# uvc_air_filter_psu.net
KiCad netlist of a schematic drawn in EAGLE
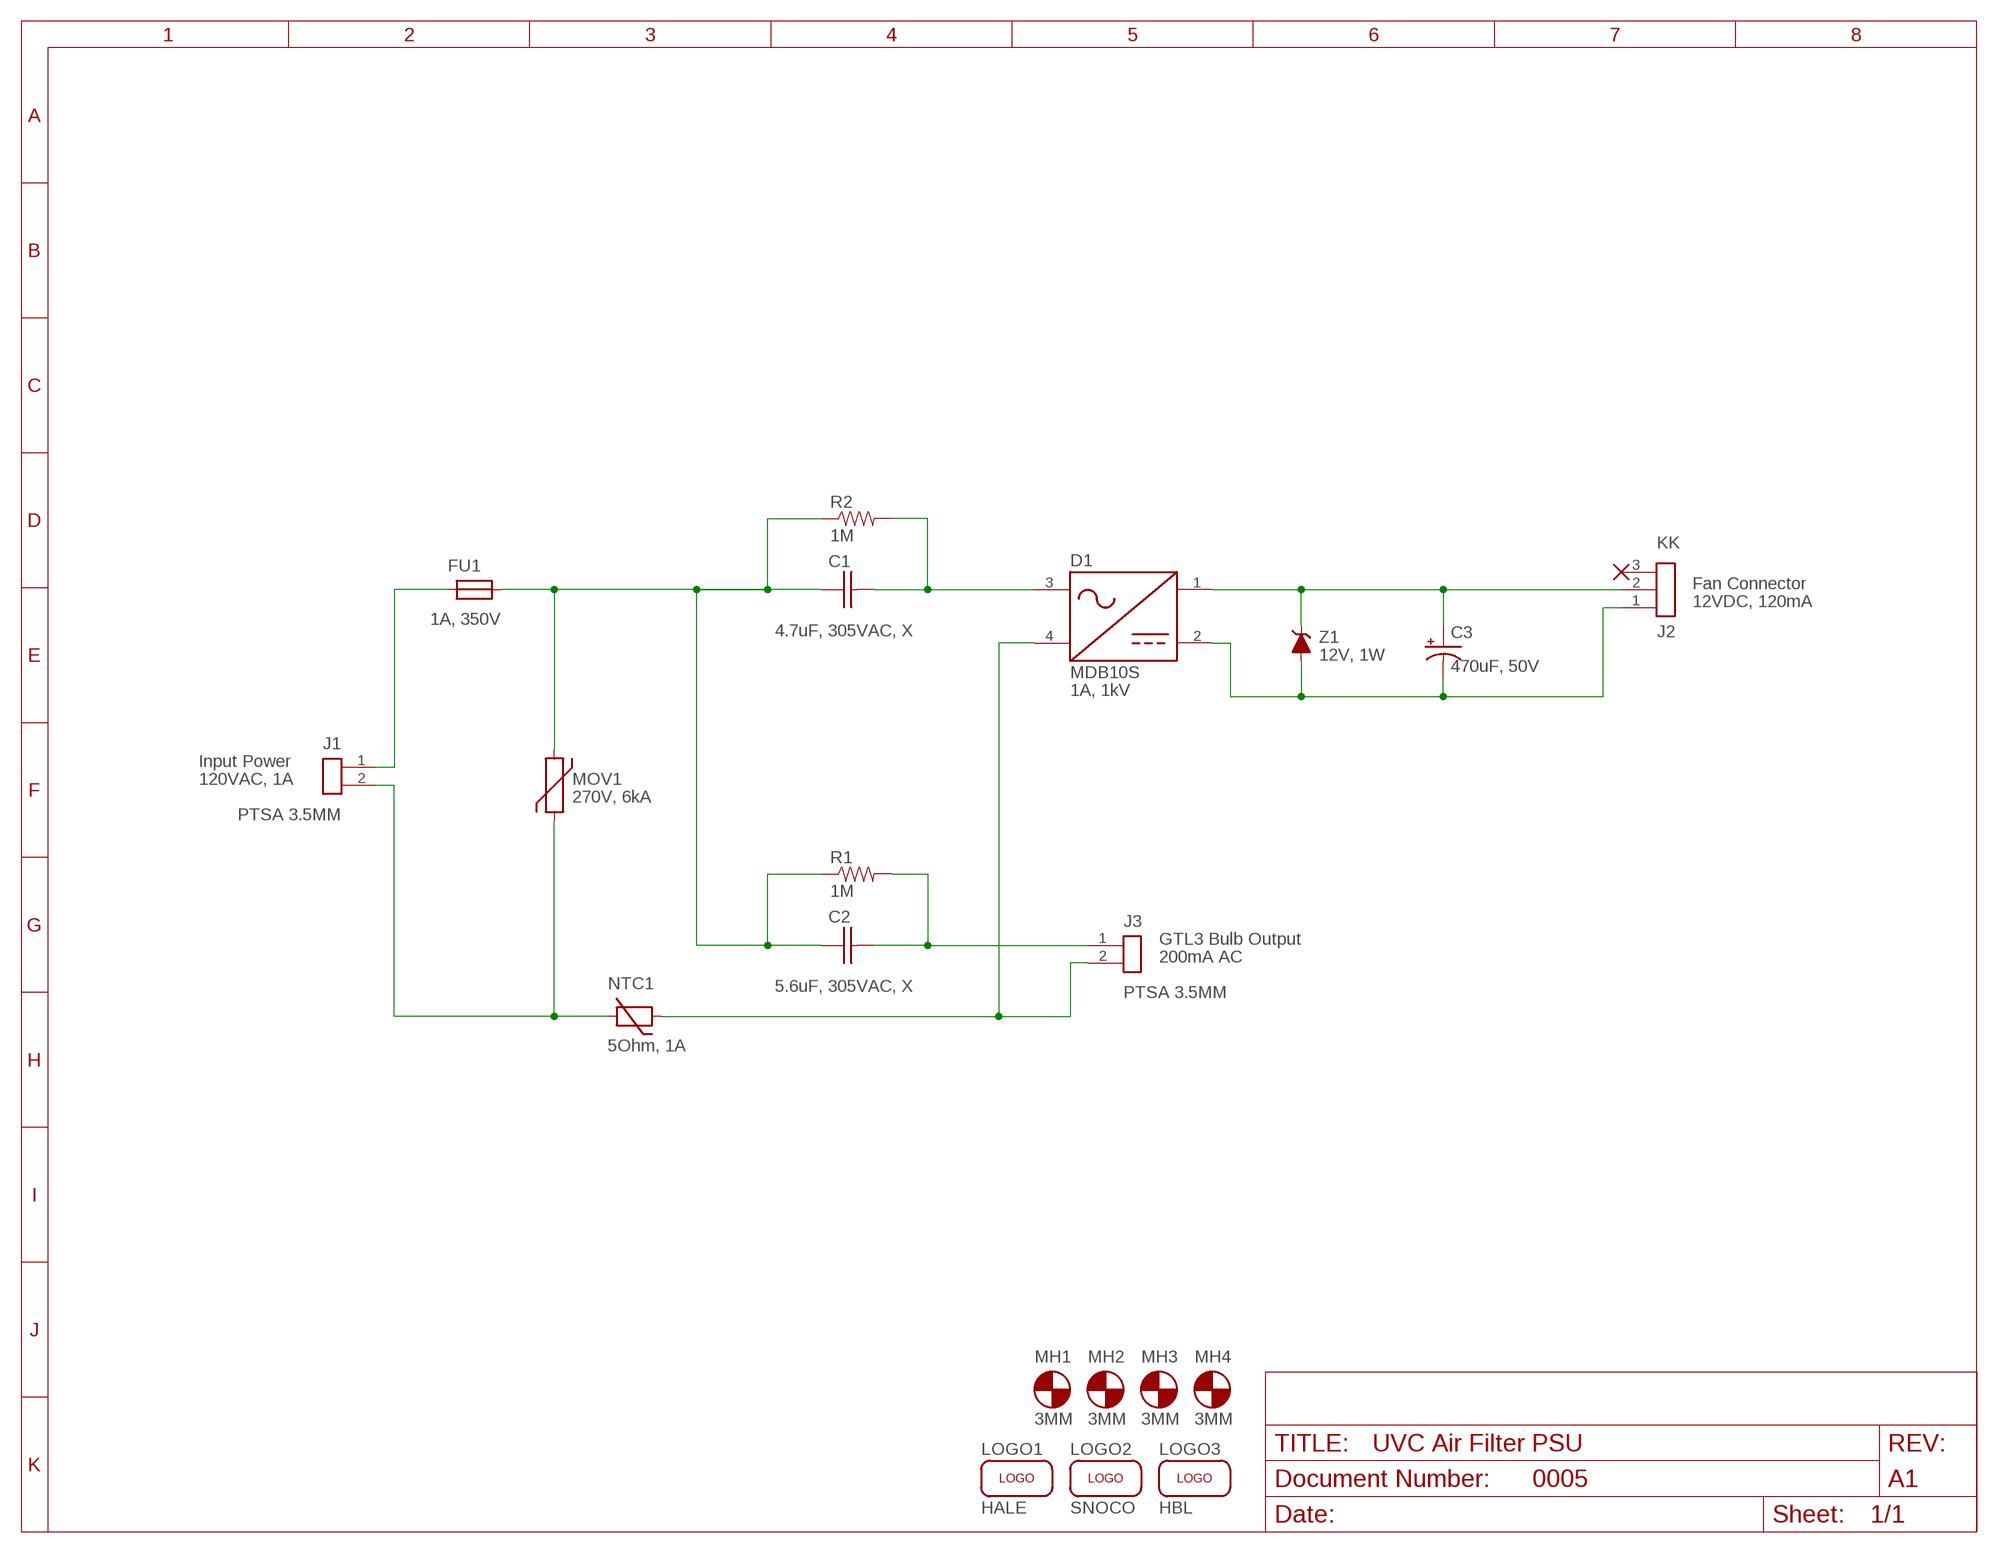
[diagram p0: schematic, sheet 1]

(export (version "E")
  (design (tool "Eeschema 10.0.6"))
  (components
    (comp (ref "C1")
      (value "4.7uF, 305VAC, X")
      (footprint "eagle-import:CAP-27.5MM")
      (fields (field (name "MFG") "TDK Electronics Inc."))
      (libsource (lib "eagle-import") (part "C-27.5MM-4.7UF/305VAC"))
    )
    (comp (ref "C2")
      (value "5.6uF, 305VAC, X")
      (footprint "eagle-import:CAP-27.5MM")
      (fields (field (name "MFG") "TDK Electronics Inc."))
      (libsource (lib "eagle-import") (part "C-27.5MM-5.6UF/305VAC"))
    )
    (comp (ref "C3")
      (value "470uF, 50V")
      (footprint "eagle-import:CAP-5MM-10MM")
      (fields
        (field (name "MFG") "Panasonic Electronic Components")
        (field (name "DIGIKEY") "P5185-ND")
        (field (name "PN") "ECA-1HM471")
      )
      (libsource (lib "eagle-import") (part "C-POL-10MM-470UF/50V"))
    )
    (comp (ref "D1")
      (value "1A, 1kV")
      (footprint "eagle-import:TSSOP-4")
      (fields (field (name "MFG") "ON Semiconductor"))
      (libsource (lib "eagle-import") (part "RECTIFIER-MDB-MDB10S"))
    )
    (comp (ref "FU1")
      (value "1A, 350V")
      (footprint "eagle-import:FUSE-5X15MM")
      (fields (field (name "MFG") "Littelfuse Inc."))
      (libsource (lib "eagle-import") (part "FUSE-TH-5X15MM-1A"))
    )
    (comp (ref "J1")
      (value "PTSA 3.5MM")
      (footprint "eagle-import:HEADER-PTSA-3.5MM-1X2")
      (fields (field (name "MFG") "Phoenix Contact"))
      (libsource (lib "eagle-import") (part "HEADER-1X2-PTSA-3.5MM"))
    )
    (comp (ref "J2")
      (value "KK")
      (footprint "eagle-import:HEADER-KK-1X3")
      (fields (field (name "MFG") "Molex"))
      (libsource (lib "eagle-import") (part "HEADER-1X3-KK"))
    )
    (comp (ref "J3")
      (value "PTSA 3.5MM")
      (footprint "eagle-import:HEADER-PTSA-3.5MM-1X2")
      (fields (field (name "MFG") "Phoenix Contact"))
      (libsource (lib "eagle-import") (part "HEADER-1X2-PTSA-3.5MM"))
    )
    (comp (ref "LOGO1")
      (value "HALE")
      (footprint "eagle-import:HALE-SILK-ICON")
      (libsource (lib "eagle-import") (part "LOGO-HALE"))
    )
    (comp (ref "LOGO2")
      (value "SNOCO")
      (footprint "eagle-import:SNOCO-SILK-ICON")
      (libsource (lib "eagle-import") (part "LOGO-SNOCO"))
    )
    (comp (ref "LOGO3")
      (value "HBL")
      (footprint "eagle-import:HACKERBOT-SILK-ICON")
      (libsource (lib "eagle-import") (part "LOGO-HACKERBOT"))
    )
    (comp (ref "MH1")
      (value "3MM")
      (footprint "eagle-import:MH-M3")
      (libsource (lib "eagle-import") (part "MH-M3"))
    )
    (comp (ref "MH2")
      (value "3MM")
      (footprint "eagle-import:MH-M3")
      (libsource (lib "eagle-import") (part "MH-M3"))
    )
    (comp (ref "MH3")
      (value "3MM")
      (footprint "eagle-import:MH-M3")
      (libsource (lib "eagle-import") (part "MH-M3"))
    )
    (comp (ref "MH4")
      (value "3MM")
      (footprint "eagle-import:MH-M3")
      (libsource (lib "eagle-import") (part "MH-M3"))
    )
    (comp (ref "MOV1")
      (value "270V, 6kA")
      (footprint "eagle-import:MOV-B722-7.5MM")
      (fields (field (name "MFG") "TDK Electronics Inc."))
      (libsource (lib "eagle-import") (part "MOV-B722-7.5MM-270V/6KA"))
    )
    (comp (ref "NTC1")
      (value "5Ohm, 1A")
      (footprint "eagle-import:MF72-D5-NTC")
      (fields (field (name "MFG") "Ametherm"))
      (libsource (lib "eagle-import") (part "NTC-5MM-TH-5OHM/1A"))
    )
    (comp (ref "R1")
      (value "1M")
      (footprint "eagle-import:1206-NONPOLAR")
      (fields
        (field (name "MFG") "Yageo")
        (field (name "DIGIKEY") "311-1.00MFRCT-ND")
        (field (name "PN") "RC1206FR-071ML")
      )
      (libsource (lib "eagle-import") (part "R-1206-15"))
    )
    (comp (ref "R2")
      (value "1M")
      (footprint "eagle-import:1206-NONPOLAR")
      (fields
        (field (name "MFG") "Yageo")
        (field (name "DIGIKEY") "311-1.00MFRCT-ND")
        (field (name "PN") "RC1206FR-071ML")
      )
      (libsource (lib "eagle-import") (part "R-1206-15"))
    )
    (comp (ref "U$1")
      (value "FRAME-8.5X11-LANDSCAPE-LET")
      (footprint "eagle-import:FRAME-8.5X11-LANDSCAPE")
      (fields (field (name "DOCNUM") "0005") (field (name "TITLE") "UVC Air Filter PSU"))
      (libsource (lib "eagle-import") (part "FRAME-8.5X11-LANDSCAPE-LET"))
    )
    (comp (ref "Z1")
      (value "12V, 1W")
      (footprint "eagle-import:SMA")
      (fields (field (name "MFG") "Diodes Incorporated"))
      (libsource (lib "eagle-import") (part "ZENER-SMA-12V/1W"))
    )
  )
  (nets
    (net (code "1") (name "Net-(C1-+)") (class "Default")
      (node (ref "C1") (pin "1") (pinfunction "+_1") (pintype "passive"))
      (node (ref "C2") (pin "1") (pinfunction "+_1") (pintype "passive"))
      (node (ref "FU1") (pin "2") (pinfunction "2_2") (pintype "passive"))
      (node (ref "MOV1") (pin "1") (pinfunction "1_1") (pintype "passive"))
      (node (ref "R1") (pin "1") (pinfunction "1_1") (pintype "passive"))
      (node (ref "R2") (pin "1") (pinfunction "1_1") (pintype "passive"))
    )
    (net (code "2") (name "Net-(C1--)") (class "Default")
      (node (ref "C1") (pin "2") (pinfunction "-_2") (pintype "passive"))
      (node (ref "D1") (pin "3") (pinfunction "1_3") (pintype "power_in"))
      (node (ref "R2") (pin "2") (pinfunction "2_2") (pintype "passive"))
    )
    (net (code "3") (name "Net-(C2--)") (class "Default")
      (node (ref "C2") (pin "2") (pinfunction "-_2") (pintype "passive"))
      (node (ref "J3") (pin "1") (pinfunction "1_1") (pintype "passive"))
      (node (ref "R1") (pin "2") (pinfunction "2_2") (pintype "passive"))
    )
    (net (code "4") (name "Net-(C3-+)") (class "Default")
      (node (ref "C3") (pin "1") (pinfunction "+_1") (pintype "passive"))
      (node (ref "D1") (pin "1") (pinfunction "+_1") (pintype "power_in"))
      (node (ref "J2") (pin "2") (pinfunction "2_2") (pintype "passive"))
      (node (ref "Z1") (pin "2") (pinfunction "C_2") (pintype "passive"))
    )
    (net (code "5") (name "Net-(C3--)") (class "Default")
      (node (ref "C3") (pin "2") (pinfunction "-_2") (pintype "passive"))
      (node (ref "D1") (pin "2") (pinfunction "-_2") (pintype "power_in"))
      (node (ref "J2") (pin "1") (pinfunction "1_1") (pintype "passive"))
      (node (ref "Z1") (pin "1") (pinfunction "A_1") (pintype "passive"))
    )
    (net (code "6") (name "Net-(D1-2)") (class "Default")
      (node (ref "D1") (pin "4") (pinfunction "2_4") (pintype "power_in"))
      (node (ref "J3") (pin "2") (pinfunction "2_2") (pintype "passive"))
      (node (ref "NTC1") (pin "2") (pinfunction "2_2") (pintype "passive"))
    )
    (net (code "7") (name "Net-(FU1-Pad1)") (class "Default")
      (node (ref "FU1") (pin "1") (pinfunction "1_1") (pintype "passive"))
      (node (ref "J1") (pin "1") (pinfunction "1_1") (pintype "passive"))
    )
    (net (code "8") (name "Net-(J1-Pad2)") (class "Default")
      (node (ref "J1") (pin "2") (pinfunction "2_2") (pintype "passive"))
      (node (ref "MOV1") (pin "2") (pinfunction "2_2") (pintype "passive"))
      (node (ref "NTC1") (pin "1") (pinfunction "1_1") (pintype "passive"))
    )
    (net (code "9") (name "unconnected-(J2-Pad3)") (class "Default")
      (node (ref "J2") (pin "3") (pinfunction "3_3") (pintype "passive"))
    )
  )
)
